# 06_iMX_8X_CAN.net
KiCad netlist of a schematic drawn in Altium Designer
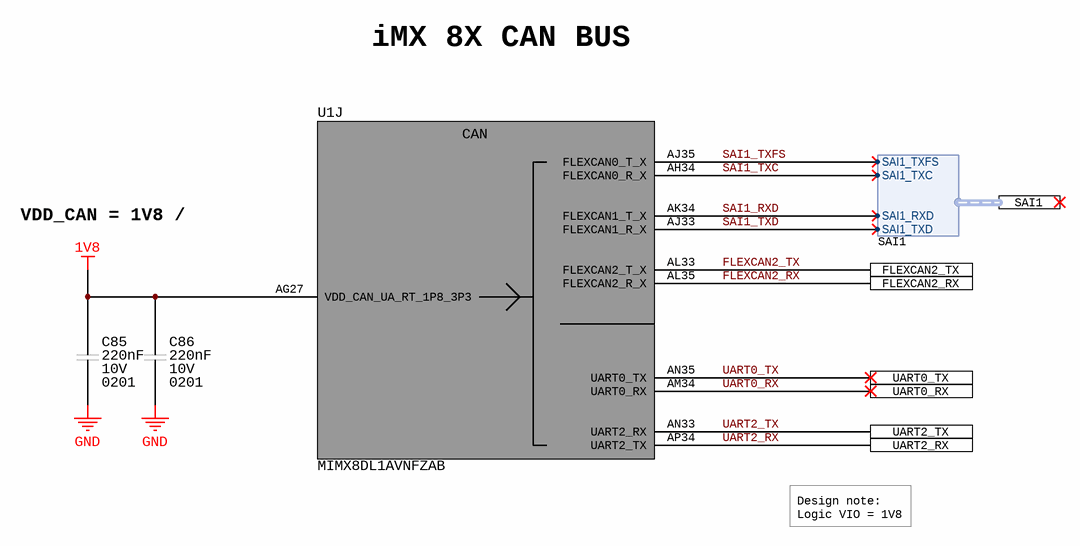
[diagram p0: 06_iMX 8X_CAN.SchDoc]

(export (version "E")
  (design (tool "Eeschema 10.0.6"))
  (components
    (comp (ref "C85")
      (value "LMK063BJ224MP-F")
      (footprint "CAP_0201_CAPC0603X03N")
      (description "Multilayer Ceramic Capacitors (High dielectric type), 10V, 0.22 uF, ± 20 %, 0201, X5R, RoHS")
      (fields
        (field (name "MANUFACTURER") "Taiyo Yuden")
        (field (name "TOLERANCE") "20%")
        (field (name "VOLTAGE RATING (DC)") "10V")
        (field (name "CAPACITANCE") "220nF")
        (field (name "CASE/PACKAGE") "0201")
      )
      (libsource (lib "Electronic Devices_LIB") (part "CAP_0.22UF_10V_X5R_0201"))
    )
    (comp (ref "C86")
      (value "LMK063BJ224MP-F")
      (footprint "CAP_0201_CAPC0603X03N")
      (description "Multilayer Ceramic Capacitors (High dielectric type), 10V, 0.22 uF, ± 20 %, 0201, X5R, RoHS")
      (fields
        (field (name "MANUFACTURER") "Taiyo Yuden")
        (field (name "TOLERANCE") "20%")
        (field (name "VOLTAGE RATING (DC)") "10V")
        (field (name "CAPACITANCE") "220nF")
        (field (name "CASE/PACKAGE") "0201")
      )
      (libsource (lib "Electronic Devices_LIB") (part "CAP_0.22UF_10V_X5R_0201"))
    )
    (comp (ref "U1")
      (value "MIMX8DL1AVNFZAB")
      (footprint "MIMX8DL1AVNFZAB")
      (description "I.MX8 Dxl 15SQ / Tray Rohs Compliant: Yes")
      (fields (field (name "MANUFACTURER") "NXP Semiconductors"))
      (libsource (lib "Electronic Devices_LIB") (part "IC_MPU_ARM_1.2GHz_MIMX8DL1AVNFZAB"))
    )
  )
  (nets
    (net (code "2") (name "/FLEXCAN2_RX") (class "Default")
      (node (ref "U1") (pin "AL35") (pinfunction "FLEXCAN2_R_X_AL35") (pintype "passive"))
    )
    (net (code "3") (name "/FLEXCAN2_TX") (class "Default")
      (node (ref "U1") (pin "AL33") (pinfunction "FLEXCAN2_T_X_AL33") (pintype "passive"))
    )
    (net (code "4") (name "/SAI1_RXD") (class "Default")
      (node (ref "U1") (pin "AK34") (pinfunction "FLEXCAN1_T_X_AK34") (pintype "passive+no_connect"))
    )
    (net (code "5") (name "/SAI1_TXC") (class "Default")
      (node (ref "U1") (pin "AH34") (pinfunction "FLEXCAN0_R_X_AH34") (pintype "passive+no_connect"))
    )
    (net (code "6") (name "/SAI1_TXD") (class "Default")
      (node (ref "U1") (pin "AJ33") (pinfunction "FLEXCAN1_R_X_AJ33") (pintype "passive+no_connect"))
    )
    (net (code "7") (name "/SAI1_TXFS") (class "Default")
      (node (ref "U1") (pin "AJ35") (pinfunction "FLEXCAN0_T_X_AJ35") (pintype "passive+no_connect"))
    )
    (net (code "8") (name "/UART0_RX") (class "Default")
      (node (ref "U1") (pin "AM34") (pinfunction "UART0_RX_AM34") (pintype "passive+no_connect"))
    )
    (net (code "9") (name "/UART0_TX") (class "Default")
      (node (ref "U1") (pin "AN35") (pinfunction "UART0_TX_AN35") (pintype "passive+no_connect"))
    )
    (net (code "10") (name "/UART2_RX") (class "Default")
      (node (ref "U1") (pin "AP34") (pinfunction "UART2_TX_AP34") (pintype "passive"))
    )
    (net (code "11") (name "/UART2_TX") (class "Default")
      (node (ref "U1") (pin "AN33") (pinfunction "UART2_RX_AN33") (pintype "passive"))
    )
    (net (code "13") (name "1V8") (class "Default")
      (node (ref "C85") (pin "2") (pinfunction "2_2") (pintype "passive"))
      (node (ref "C86") (pin "2") (pinfunction "2_2") (pintype "passive"))
      (node (ref "U1") (pin "AG27") (pinfunction "VDD_CAN_UA_RT_1P8_3P3_AG27") (pintype "passive"))
    )
    (net (code "14") (name "GND") (class "Default")
      (node (ref "C85") (pin "1") (pinfunction "1_1") (pintype "passive"))
      (node (ref "C86") (pin "1") (pinfunction "1_1") (pintype "passive"))
    )
  )
)
